# PX4FLOW2_1_Connectors_X0.net
KiCad netlist of a schematic drawn in Altium Designer
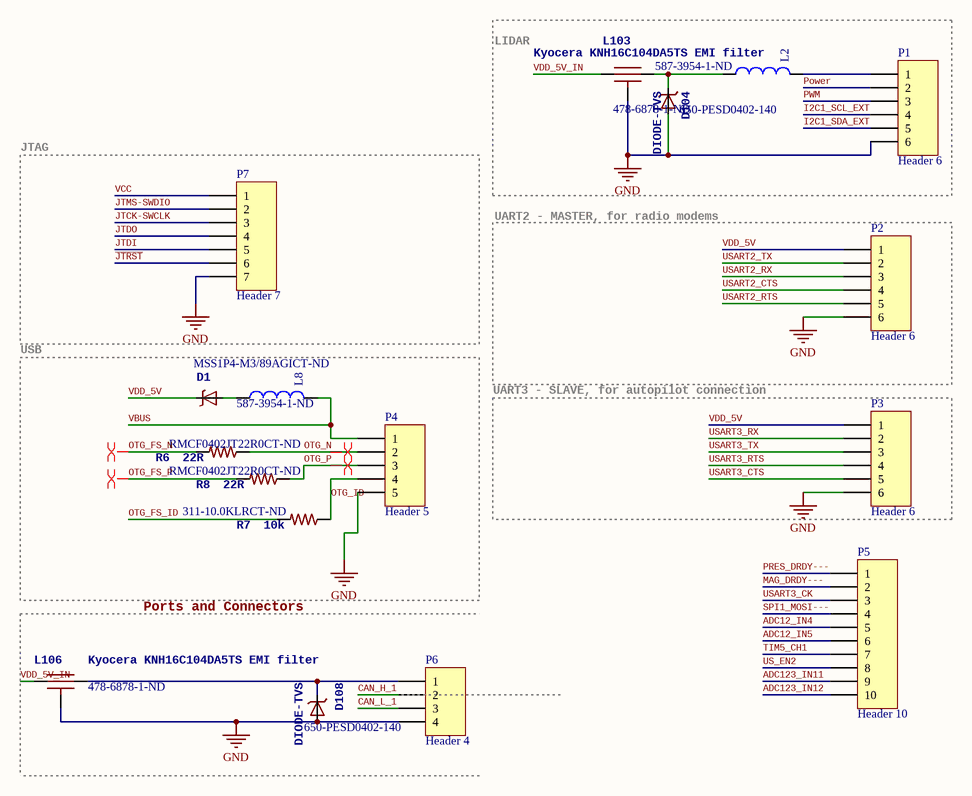
[diagram p0: PX4FLOW2.1_Connectors_X0.SchDoc]

(export (version "E")
  (design (tool "Eeschema 10.0.6"))
  (components
    (comp (ref "D1")
      (value "MSS1P4-M3")
      (footprint "MICROSMP")
      (description "Schottky barrier diode in DO214AC, e.g. Fairchild SS14.")
      (fields (field (name "SUPPLIER PART NUMBER 1") "MSS1P4-M3/89AGICT-ND"))
      (libsource (lib "pixhawk2") (part "DIODE-SCHOTTKY_MSMP"))
    )
    (comp (ref "D104")
      (value "DIODE-TVS")
      (footprint "0402-TVS")
      (description "Diode, TVS, 14VWM, 40VC, 0402, SMD")
      (fields
        (field (name "SUPPLIER PART NUMBER 1") "650-PESD0402-140")
        (field (name "3DR_PARTNO") "ECM0837")
      )
      (libsource (lib "PCA_0005_FULL_CB_REV_A") (part "DIODE-TVS"))
    )
    (comp (ref "D108")
      (value "DIODE-TVS")
      (footprint "0402-TVS")
      (description "Diode, TVS, 14VWM, 40VC, 0402, SMD")
      (fields
        (field (name "SUPPLIER PART NUMBER 1") "650-PESD0402-140")
        (field (name "3DR_PARTNO") "ECM0837")
      )
      (libsource (lib "PCA_0005_FULL_CB_REV_A") (part "DIODE-TVS"))
    )
    (comp (ref "L2")
      (value "Inductor")
      (footprint "L0402")
      (description "FERRITE BEAD 120 OHM 0402")
      (fields (field (name "SUPPLIER PART NUMBER 1") "587-3954-1-ND"))
      (libsource (lib "3DR") (part "Inductor"))
    )
    (comp (ref "L8")
      (value "FERRITE BEAD 120 OHM 0402")
      (footprint "L0402")
      (fields (field (name "SUPPLIER PART NUMBER 1") "587-3954-1-ND"))
      (libsource (lib "3DR") (part "Inductor"))
    )
    (comp (ref "L103")
      (value "Kyocera KNH16C104DA5TS EMI filter")
      (footprint "KYOCERA-KNH16-DA")
      (description "Capacitor, Filter, 0.1uF, 25V, 2A, 0603, SMD")
      (fields (field (name "SUPPLIER PART NUMBER 1") "478-6878-1-ND") (field (name "3DR_PARTNO") "ECM0719"))
      (libsource (lib "PCA_0005_FULL_CB_REV_A") (part "KNH16C104DA5TS"))
    )
    (comp (ref "L106")
      (value "Kyocera KNH16C104DA5TS EMI filter")
      (footprint "KYOCERA-KNH16-DA")
      (description "Capacitor, Filter, 0.1uF, 25V, 2A, 0603, SMD")
      (fields (field (name "SUPPLIER PART NUMBER 1") "478-6878-1-ND") (field (name "3DR_PARTNO") "ECM0719"))
      (libsource (lib "PCA_0005_FULL_CB_REV_A") (part "KNH16C104DA5TS"))
    )
    (comp (ref "P1")
      (value "Header 6")
      (footprint "HDR1X6")
      (description "Header, 6-Pin")
      (fields (field (name "PUBLISHER") "Altium Limited"))
      (libsource (lib "Miscellaneous Connectors") (part "Header 6"))
    )
    (comp (ref "P2")
      (value "Header 6")
      (footprint "HDR1X6")
      (description "Header, 6-Pin")
      (fields (field (name "PUBLISHER") "Altium Limited"))
      (libsource (lib "Miscellaneous Connectors") (part "Header 6"))
    )
    (comp (ref "P3")
      (value "Header 6")
      (footprint "HDR1X6")
      (description "Header, 6-Pin")
      (fields (field (name "PUBLISHER") "Altium Limited"))
      (libsource (lib "Miscellaneous Connectors") (part "Header 6"))
    )
    (comp (ref "P4")
      (value "Header 5")
      (footprint "HDR1X5")
      (description "Header, 5-Pin")
      (fields (field (name "PUBLISHER") "Altium Limited"))
      (libsource (lib "Miscellaneous Connectors") (part "Header 5"))
    )
    (comp (ref "P5")
      (value "Header 10")
      (footprint "HDR1X10")
      (description "Header, 10-Pin")
      (fields (field (name "PUBLISHER") "Altium Limited"))
      (libsource (lib "Miscellaneous Connectors") (part "Header 10"))
    )
    (comp (ref "P6")
      (value "Header 4")
      (footprint "HDR1X4")
      (description "Header, 4-Pin")
      (fields (field (name "PUBLISHER") "Altium Limited"))
      (libsource (lib "Miscellaneous Connectors") (part "Header 4"))
    )
    (comp (ref "P7")
      (value "Header 7")
      (footprint "HDR1X7")
      (description "Header, 7-Pin")
      (fields (field (name "PUBLISHER") "Altium Limited"))
      (libsource (lib "Miscellaneous Connectors") (part "Header 7"))
    )
    (comp (ref "R6")
      (value "22R")
      (footprint "R0402")
      (fields
        (field (name "PARTNO") "RMCF0402JT22R0")
        (field (name "SUPPLIER PART NUMBER 1") "RMCF0402JT22R0CT-ND")
      )
      (libsource (lib "pixhawk2") (part "RESISTOR0402-RES"))
    )
    (comp (ref "R7")
      (value "10k")
      (footprint "R0402")
      (description "RES 10K OHM 1/16W 1% 0402 SMD")
      (fields
        (field (name "PARTNO") "MFR-25FBF-10K0")
        (field (name "SUPPLIER PART NUMBER 1") "311-10.0KLRCT-ND")
      )
      (libsource (lib "pixhawk2") (part "RESISTOR0402-RES"))
    )
    (comp (ref "R8")
      (value "22R")
      (footprint "R0402")
      (fields
        (field (name "PARTNO") "RMCF0402JT22R0")
        (field (name "SUPPLIER PART NUMBER 1") "RMCF0402JT22R0CT-ND")
      )
      (libsource (lib "pixhawk2") (part "RESISTOR0402-RES"))
    )
  )
  (nets
    (net (code "1") (name "/ADC12_IN4") (class "Default")
      (node (ref "P5") (pin "5") (pinfunction "5_5") (pintype "passive"))
    )
    (net (code "2") (name "/ADC12_IN5") (class "Default")
      (node (ref "P5") (pin "6") (pinfunction "6_6") (pintype "passive"))
    )
    (net (code "3") (name "/ADC123_IN11") (class "Default")
      (node (ref "P5") (pin "9") (pinfunction "9_9") (pintype "passive"))
    )
    (net (code "4") (name "/ADC123_IN12") (class "Default")
      (node (ref "P5") (pin "10") (pinfunction "10_10") (pintype "passive"))
    )
    (net (code "5") (name "/CAN_H_1") (class "Default")
      (node (ref "P6") (pin "2") (pinfunction "2_2") (pintype "passive"))
    )
    (net (code "6") (name "/CAN_L_1") (class "Default")
      (node (ref "P6") (pin "3") (pinfunction "3_3") (pintype "passive"))
    )
    (net (code "7") (name "/I2C1_SCL_EXT") (class "Default")
      (node (ref "P1") (pin "4") (pinfunction "4_4") (pintype "passive"))
    )
    (net (code "8") (name "/I2C1_SDA_EXT") (class "Default")
      (node (ref "P1") (pin "5") (pinfunction "5_5") (pintype "passive"))
    )
    (net (code "9") (name "/JTCK-SWCLK") (class "Default")
      (node (ref "P7") (pin "3") (pinfunction "3_3") (pintype "passive"))
    )
    (net (code "10") (name "/JTDI") (class "Default")
      (node (ref "P7") (pin "5") (pinfunction "5_5") (pintype "passive"))
    )
    (net (code "11") (name "/JTDO") (class "Default")
      (node (ref "P7") (pin "4") (pinfunction "4_4") (pintype "passive"))
    )
    (net (code "12") (name "/JTMS-SWDIO") (class "Default")
      (node (ref "P7") (pin "2") (pinfunction "2_2") (pintype "passive"))
    )
    (net (code "13") (name "/MAG_DRDY---") (class "Default")
      (node (ref "P5") (pin "2") (pinfunction "2_2") (pintype "passive"))
    )
    (net (code "14") (name "/OTG_FS_ID") (class "Default")
      (node (ref "R7") (pin "2") (pinfunction "2_2") (pintype "passive"))
    )
    (net (code "15") (name "/OTG_FS_N") (class "Default")
      (node (ref "R6") (pin "2") (pinfunction "2_2") (pintype "passive"))
    )
    (net (code "16") (name "/OTG_FS_P") (class "Default")
      (node (ref "R8") (pin "2") (pinfunction "2_2") (pintype "passive"))
    )
    (net (code "17") (name "/OTG_ID") (class "Default")
      (node (ref "P4") (pin "4") (pinfunction "4_4") (pintype "passive"))
      (node (ref "R7") (pin "1") (pinfunction "1_1") (pintype "passive"))
    )
    (net (code "18") (name "/OTG_N") (class "Default")
      (node (ref "P4") (pin "2") (pinfunction "2_2") (pintype "passive"))
      (node (ref "R6") (pin "1") (pinfunction "1_1") (pintype "passive"))
    )
    (net (code "19") (name "/OTG_P") (class "Default")
      (node (ref "P4") (pin "3") (pinfunction "3_3") (pintype "passive"))
      (node (ref "R8") (pin "1") (pinfunction "1_1") (pintype "passive"))
    )
    (net (code "20") (name "/PRES_DRDY---") (class "Default")
      (node (ref "P5") (pin "1") (pinfunction "1_1") (pintype "passive"))
    )
    (net (code "21") (name "/PWM") (class "Default")
      (node (ref "P1") (pin "3") (pinfunction "3_3") (pintype "passive"))
    )
    (net (code "22") (name "/Power") (class "Default")
      (node (ref "P1") (pin "2") (pinfunction "2_2") (pintype "passive"))
    )
    (net (code "23") (name "/SPI1_MOSI---") (class "Default")
      (node (ref "P5") (pin "4") (pinfunction "4_4") (pintype "passive"))
    )
    (net (code "24") (name "/TIM5_CH1") (class "Default")
      (node (ref "P5") (pin "7") (pinfunction "7_7") (pintype "passive"))
    )
    (net (code "25") (name "/USART2_CTS") (class "Default")
      (node (ref "P2") (pin "4") (pinfunction "4_4") (pintype "passive"))
    )
    (net (code "26") (name "/USART2_RTS") (class "Default")
      (node (ref "P2") (pin "5") (pinfunction "5_5") (pintype "passive"))
    )
    (net (code "27") (name "/USART2_RX") (class "Default")
      (node (ref "P2") (pin "3") (pinfunction "3_3") (pintype "passive"))
    )
    (net (code "28") (name "/USART2_TX") (class "Default")
      (node (ref "P2") (pin "2") (pinfunction "2_2") (pintype "passive"))
    )
    (net (code "29") (name "/USART3_CK") (class "Default")
      (node (ref "P5") (pin "3") (pinfunction "3_3") (pintype "passive"))
    )
    (net (code "30") (name "/USART3_CTS") (class "Default")
      (node (ref "P3") (pin "5") (pinfunction "5_5") (pintype "passive"))
    )
    (net (code "31") (name "/USART3_RTS") (class "Default")
      (node (ref "P3") (pin "4") (pinfunction "4_4") (pintype "passive"))
    )
    (net (code "32") (name "/USART3_RX") (class "Default")
      (node (ref "P3") (pin "2") (pinfunction "2_2") (pintype "passive"))
    )
    (net (code "33") (name "/USART3_TX") (class "Default")
      (node (ref "P3") (pin "3") (pinfunction "3_3") (pintype "passive"))
    )
    (net (code "34") (name "/US_EN2") (class "Default")
      (node (ref "P5") (pin "8") (pinfunction "8_8") (pintype "passive"))
    )
    (net (code "35") (name "/VBUS") (class "Default")
      (node (ref "L8") (pin "2") (pinfunction "2_2") (pintype "passive"))
      (node (ref "P4") (pin "1") (pinfunction "1_1") (pintype "passive"))
    )
    (net (code "36") (name "/VCC") (class "Default")
      (node (ref "P7") (pin "1") (pinfunction "1_1") (pintype "passive"))
    )
    (net (code "37") (name "/VDD_5V") (class "Default")
      (node (ref "D1") (pin "CATHODE") (pinfunction "C_CATHODE") (pintype "passive"))
      (node (ref "P2") (pin "1") (pinfunction "1_1") (pintype "passive"))
      (node (ref "P3") (pin "1") (pinfunction "1_1") (pintype "passive"))
    )
    (net (code "38") (name "/VDD_5V_IN") (class "Default")
      (node (ref "L103") (pin "P$1") (pinfunction "P$1_P$1") (pintype "passive"))
      (node (ref "L106") (pin "P$1") (pinfunction "P$1_P$1") (pintype "passive"))
    )
    (net (code "39") (name "/~{JTRST}") (class "Default")
      (node (ref "P7") (pin "6") (pinfunction "6_6") (pintype "passive"))
    )
    (net (code "40") (name "GND") (class "Default")
      (node (ref "D104") (pin "A") (pinfunction "A_A") (pintype "passive"))
      (node (ref "D108") (pin "A") (pinfunction "A_A") (pintype "passive"))
      (node (ref "L103") (pin "GND") (pinfunction "GND_GND") (pintype "passive"))
      (node (ref "L106") (pin "GND") (pinfunction "GND_GND") (pintype "passive"))
      (node (ref "P1") (pin "6") (pinfunction "6_6") (pintype "passive"))
      (node (ref "P2") (pin "6") (pinfunction "6_6") (pintype "passive"))
      (node (ref "P3") (pin "6") (pinfunction "6_6") (pintype "passive"))
      (node (ref "P4") (pin "5") (pinfunction "5_5") (pintype "passive"))
      (node (ref "P6") (pin "4") (pinfunction "4_4") (pintype "passive"))
      (node (ref "P7") (pin "7") (pinfunction "7_7") (pintype "passive"))
    )
    (net (code "41") (name "Net-(D1-A)") (class "Default")
      (node (ref "D1") (pin "ANODE") (pinfunction "A_ANODE") (pintype "passive"))
      (node (ref "L8") (pin "1") (pinfunction "1_1") (pintype "passive"))
    )
    (net (code "42") (name "Net-(D104-PadC)") (class "Default")
      (node (ref "D104") (pin "C") (pinfunction "C_C") (pintype "passive"))
      (node (ref "L103") (pin "P$2") (pinfunction "P$2_P$2") (pintype "passive"))
      (node (ref "L2") (pin "1") (pinfunction "1_1") (pintype "passive"))
    )
    (net (code "43") (name "Net-(D108-PadC)") (class "Default")
      (node (ref "D108") (pin "C") (pinfunction "C_C") (pintype "passive"))
      (node (ref "L106") (pin "P$2") (pinfunction "P$2_P$2") (pintype "passive"))
      (node (ref "P6") (pin "1") (pinfunction "1_1") (pintype "passive"))
    )
    (net (code "44") (name "Net-(L2-Pad2)") (class "Default")
      (node (ref "L2") (pin "2") (pinfunction "2_2") (pintype "passive"))
      (node (ref "P1") (pin "1") (pinfunction "1_1") (pintype "passive"))
    )
  )
)
